# POWR0001_BCR_LT1513.net
KiCad netlist of a schematic drawn in Altium Designer
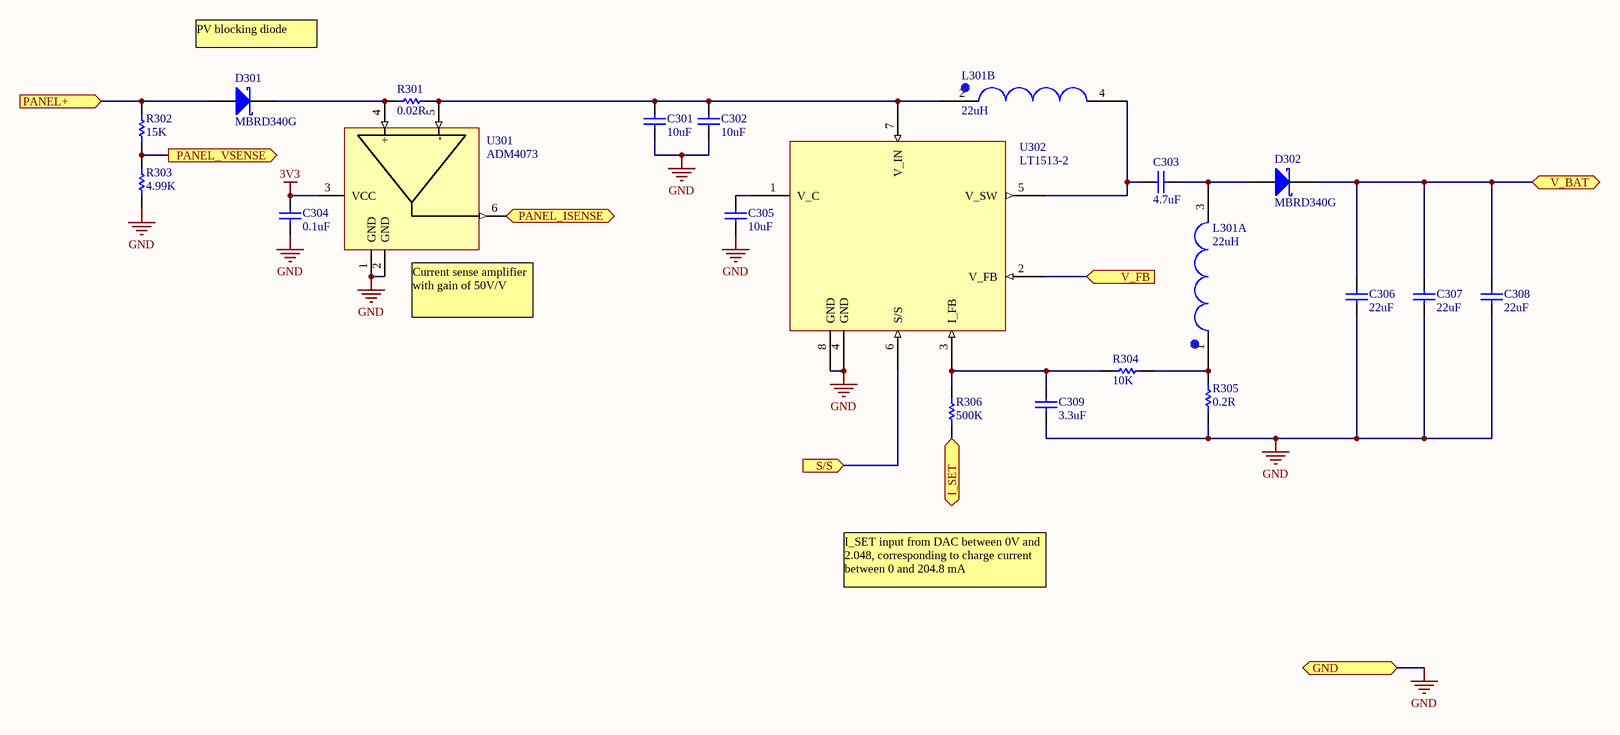
[diagram p0: POWR0001_BCR_LT1513.SchDoc]

(export (version "E")
  (design (tool "Eeschema 10.0.6"))
  (components
    (comp (ref "C301")
      (value "10uF")
      (footprint "CAPC3225M")
      (description "Capacitor")
      (fields (field (name "Comment") "Cap") (field (name "PUBLISHER") "Altium Limited"))
      (libsource (lib "Miscellaneous Devices") (part "Cap"))
    )
    (comp (ref "C302")
      (value "10uF")
      (footprint "CAPC3225M")
      (description "Capacitor")
      (fields (field (name "Comment") "Cap") (field (name "PUBLISHER") "Altium Limited"))
      (libsource (lib "Miscellaneous Devices") (part "Cap"))
    )
    (comp (ref "C303")
      (value "4.7uF")
      (footprint "CAPC3225M")
      (description "Capacitor")
      (fields (field (name "Comment") "Cap") (field (name "PUBLISHER") "Altium Limited"))
      (libsource (lib "Miscellaneous Devices") (part "Cap"))
    )
    (comp (ref "C304")
      (value "0.1uF")
      (footprint "CAPC2012M")
      (description "Capacitor")
      (fields (field (name "Comment") "Cap") (field (name "PUBLISHER") "Altium Limited"))
      (libsource (lib "Miscellaneous Devices") (part "Cap"))
    )
    (comp (ref "C305")
      (value "10uF")
      (footprint "CAPC3216M")
      (description "Capacitor")
      (fields (field (name "Comment") "Cap") (field (name "PUBLISHER") "Altium Limited"))
      (libsource (lib "Miscellaneous Devices") (part "Cap"))
    )
    (comp (ref "C306")
      (value "22uF")
      (footprint "CAPC4532M")
      (description "Capacitor")
      (fields (field (name "Comment") "Cap") (field (name "PUBLISHER") "Altium Limited"))
      (libsource (lib "Miscellaneous Devices") (part "Cap"))
    )
    (comp (ref "C307")
      (value "22uF")
      (footprint "CAPC4532M")
      (description "Capacitor")
      (fields (field (name "Comment") "Cap") (field (name "PUBLISHER") "Altium Limited"))
      (libsource (lib "Miscellaneous Devices") (part "Cap"))
    )
    (comp (ref "C308")
      (value "22uF")
      (footprint "CAPC4532M")
      (description "Capacitor")
      (fields (field (name "Comment") "Cap") (field (name "PUBLISHER") "Altium Limited"))
      (libsource (lib "Miscellaneous Devices") (part "Cap"))
    )
    (comp (ref "C309")
      (value "3.3uF")
      (footprint "CAPC3216M")
      (description "Capacitor")
      (fields (field (name "Comment") "Cap") (field (name "PUBLISHER") "Altium Limited"))
      (libsource (lib "Miscellaneous Devices") (part "Cap"))
    )
    (comp (ref "D301")
      (value "MBRD340G")
      (footprint "TO229P990X238-3N")
      (description "Schottky Rectifier")
      (fields (field (name "PUBLISHER") "Altium Limited"))
      (libsource (lib "Miscellaneous Devices") (part "Diode 11DQ03"))
    )
    (comp (ref "D302")
      (value "MBRD340G")
      (footprint "TO229P990X238-3N")
      (description "Schottky Rectifier")
      (fields (field (name "PUBLISHER") "Altium Limited"))
      (libsource (lib "Miscellaneous Devices") (part "Diode 11DQ03"))
    )
    (comp (ref "L301")
      (value "22uH")
      (footprint "DRQ125")
      (fields (field (name "Comment") "DRQ125 Dual Inductor"))
      (libsource (lib "LT1513") (part "DRQ125 Dual Inductor"))
    )
    (comp (ref "R301")
      (value "0.02R")
      (footprint "RESC2012M")
      (description "Resistor")
      (fields (field (name "Comment") "Res1") (field (name "PUBLISHER") "Altium Limited"))
      (libsource (lib "Miscellaneous Devices") (part "Res1"))
    )
    (comp (ref "R302")
      (value "15K")
      (footprint "RESC2012M")
      (description "Resistor")
      (fields (field (name "Comment") "Res1") (field (name "PUBLISHER") "Altium Limited"))
      (libsource (lib "Miscellaneous Devices") (part "Res1"))
    )
    (comp (ref "R303")
      (value "4.99K")
      (footprint "RESC2012M")
      (description "Resistor")
      (fields (field (name "Comment") "Res1") (field (name "PUBLISHER") "Altium Limited"))
      (libsource (lib "Miscellaneous Devices") (part "Res1"))
    )
    (comp (ref "R304")
      (value "10K")
      (footprint "RESC2012M")
      (description "Resistor")
      (fields (field (name "Comment") "Res1") (field (name "PUBLISHER") "Altium Limited"))
      (libsource (lib "Miscellaneous Devices") (part "Res1"))
    )
    (comp (ref "R305")
      (value "0.2R")
      (footprint "RESC2012M")
      (description "Resistor")
      (fields (field (name "Comment") "Res1") (field (name "PUBLISHER") "Altium Limited"))
      (libsource (lib "Miscellaneous Devices") (part "Res1"))
    )
    (comp (ref "R306")
      (value "500K")
      (footprint "RESC2012M")
      (description "Resistor")
      (fields (field (name "Comment") "Res1") (field (name "PUBLISHER") "Altium Limited"))
      (libsource (lib "Miscellaneous Devices") (part "Res1"))
    )
    (comp (ref "U301")
      (value "ADM4073")
      (footprint "SOT26A-6N")
      (description "Current Sense Amplifer")
      (libsource (lib "Schlib1") (part "ADM4073"))
    )
    (comp (ref "U302")
      (value "LT1513-2")
      (footprint "LT1513-2_TO127P1420-8N")
      (libsource (lib "BCR") (part "LT1513-2"))
    )
  )
  (nets
    (net (code "1") (name "/I_SET") (class "Default")
      (node (ref "R306") (pin "2") (pinfunction "2_2") (pintype "passive"))
    )
    (net (code "2") (name "/PANEL+") (class "Default")
      (node (ref "D301") (pin "1") (pinfunction "A_1") (pintype "passive"))
      (node (ref "R302") (pin "2") (pinfunction "2_2") (pintype "passive"))
    )
    (net (code "3") (name "/PANEL_ISENSE") (class "Default") (node (ref "U301") (pin "6") (pintype "output")))
    (net (code "4") (name "/PANEL_VSENSE") (class "Default")
      (node (ref "R302") (pin "1") (pinfunction "1_1") (pintype "passive"))
      (node (ref "R303") (pin "2") (pinfunction "2_2") (pintype "passive"))
    )
    (net (code "5") (name "/S{slash}S") (class "Default")
      (node (ref "U302") (pin "6") (pinfunction "S/S_6") (pintype "input"))
    )
    (net (code "6") (name "/V_BAT") (class "Default")
      (node (ref "C306") (pin "1") (pinfunction "1_1") (pintype "passive"))
      (node (ref "C307") (pin "1") (pinfunction "1_1") (pintype "passive"))
      (node (ref "C308") (pin "1") (pinfunction "1_1") (pintype "passive"))
      (node (ref "D302") (pin "2") (pinfunction "K_2") (pintype "passive"))
    )
    (net (code "7") (name "/V_FB") (class "Default")
      (node (ref "U302") (pin "2") (pinfunction "V_FB_2") (pintype "input"))
    )
    (net (code "8") (name "3V3") (class "Default")
      (node (ref "C304") (pin "1") (pinfunction "1_1") (pintype "passive"))
      (node (ref "U301") (pin "3") (pinfunction "VCC_3") (pintype "passive"))
    )
    (net (code "9") (name "GND") (class "Default")
      (node (ref "C301") (pin "2") (pinfunction "2_2") (pintype "passive"))
      (node (ref "C302") (pin "2") (pinfunction "2_2") (pintype "passive"))
      (node (ref "C304") (pin "2") (pinfunction "2_2") (pintype "passive"))
      (node (ref "C305") (pin "2") (pinfunction "2_2") (pintype "passive"))
      (node (ref "C306") (pin "2") (pinfunction "2_2") (pintype "passive"))
      (node (ref "C307") (pin "2") (pinfunction "2_2") (pintype "passive"))
      (node (ref "C308") (pin "2") (pinfunction "2_2") (pintype "passive"))
      (node (ref "C309") (pin "1") (pinfunction "1_1") (pintype "passive"))
      (node (ref "R303") (pin "1") (pinfunction "1_1") (pintype "passive"))
      (node (ref "R305") (pin "1") (pinfunction "1_1") (pintype "passive"))
      (node (ref "U301") (pin "1") (pinfunction "GND_1") (pintype "passive"))
      (node (ref "U301") (pin "2") (pinfunction "GND_2") (pintype "passive"))
      (node (ref "U302") (pin "4") (pinfunction "GND_4") (pintype "passive"))
      (node (ref "U302") (pin "8") (pinfunction "GND_8") (pintype "passive"))
    )
    (net (code "10") (name "Net-(D301-K)") (class "Default")
      (node (ref "D301") (pin "2") (pinfunction "K_2") (pintype "passive"))
      (node (ref "R301") (pin "2") (pinfunction "2_2") (pintype "passive"))
      (node (ref "U301") (pin "4") (pinfunction "+_4") (pintype "input"))
    )
    (net (code "11") (name "Net-(D302-A)") (class "Default")
      (node (ref "C303") (pin "1") (pinfunction "1_1") (pintype "passive"))
      (node (ref "D302") (pin "1") (pinfunction "A_1") (pintype "passive"))
      (node (ref "L301") (pin "3") (pinfunction "18_3") (pintype "passive"))
    )
    (net (code "12") (name "Net-(L301A-17)") (class "Default")
      (node (ref "L301") (pin "1") (pinfunction "17_1") (pintype "passive"))
      (node (ref "R304") (pin "1") (pinfunction "1_1") (pintype "passive"))
      (node (ref "R305") (pin "2") (pinfunction "2_2") (pintype "passive"))
    )
    (net (code "13") (name "Net-(L301B-17)") (class "Default")
      (node (ref "C301") (pin "1") (pinfunction "1_1") (pintype "passive"))
      (node (ref "C302") (pin "1") (pinfunction "1_1") (pintype "passive"))
      (node (ref "L301") (pin "2") (pinfunction "17_2") (pintype "passive"))
      (node (ref "R301") (pin "1") (pinfunction "1_1") (pintype "passive"))
      (node (ref "U301") (pin "5") (pinfunction "-_5") (pintype "input"))
      (node (ref "U302") (pin "7") (pinfunction "V_IN_7") (pintype "input"))
    )
    (net (code "14") (name "Net-(L301B-18)") (class "Default")
      (node (ref "C303") (pin "2") (pinfunction "2_2") (pintype "passive"))
      (node (ref "L301") (pin "4") (pinfunction "18_4") (pintype "passive"))
      (node (ref "U302") (pin "5") (pinfunction "V_SW_5") (pintype "output"))
    )
    (net (code "15") (name "Net-(U302-I_FB)") (class "Default")
      (node (ref "C309") (pin "2") (pinfunction "2_2") (pintype "passive"))
      (node (ref "R304") (pin "2") (pinfunction "2_2") (pintype "passive"))
      (node (ref "R306") (pin "1") (pinfunction "1_1") (pintype "passive"))
      (node (ref "U302") (pin "3") (pinfunction "I_FB_3") (pintype "input"))
    )
    (net (code "16") (name "Net-(U302-V_C)") (class "Default")
      (node (ref "C305") (pin "1") (pinfunction "1_1") (pintype "passive"))
      (node (ref "U302") (pin "1") (pinfunction "V_C_1") (pintype "passive"))
    )
  )
)
